# PROJECT_BEL_RUMAH.net
KiCad netlist of a schematic drawn in EAGLE
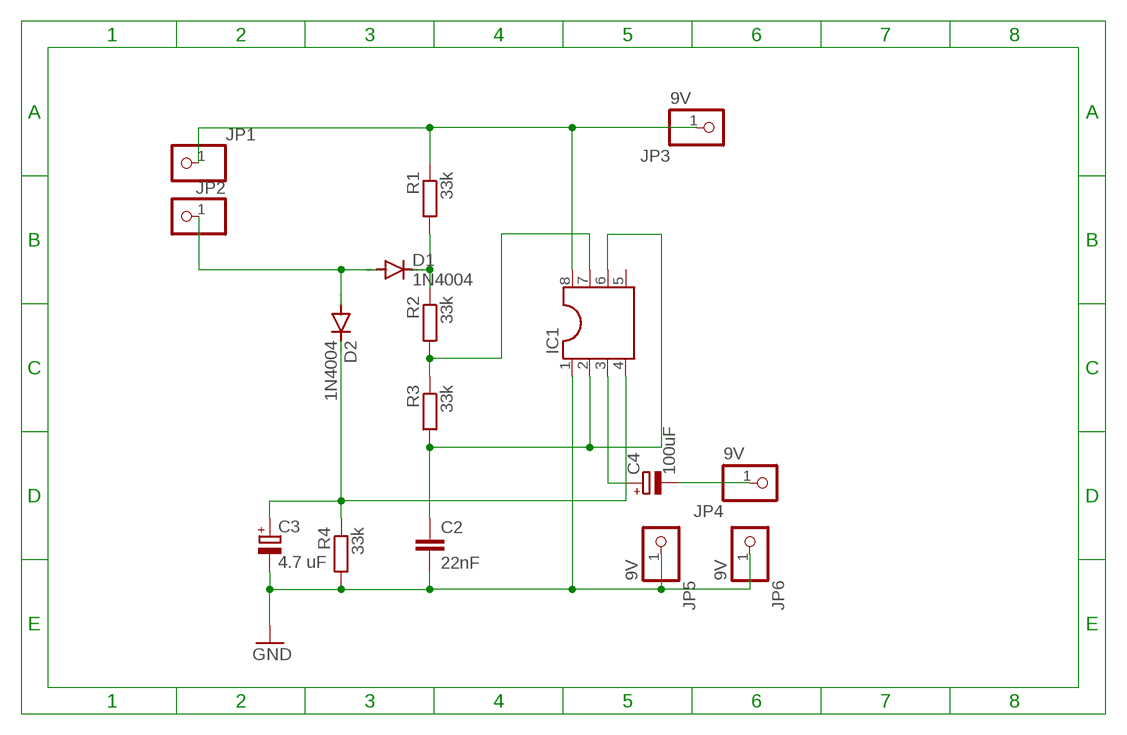
[diagram p0: schematic, sheet 1]

(export (version "E")
  (design (tool "Eeschema 10.0.6"))
  (components
    (comp (ref "C2")
      (value "22nF")
      (footprint "eagle-import:C025-024X044")
      (libsource (lib "eagle-import") (part "C-EU025-024X044"))
    )
    (comp (ref "C3")
      (value "4.7 uF")
      (footprint "eagle-import:E2,5-6E")
      (libsource (lib "eagle-import") (part "CPOL-EUE2,5-6E"))
    )
    (comp (ref "C4")
      (value "100uF")
      (footprint "eagle-import:E2,5-6E")
      (libsource (lib "eagle-import") (part "CPOL-EUE2,5-6E"))
    )
    (comp (ref "D1")
      (value "1N4004")
      (footprint "eagle-import:DO41-10")
      (libsource (lib "eagle-import") (part "1N4004"))
    )
    (comp (ref "D2")
      (value "1N4004")
      (footprint "eagle-import:DO41-10")
      (libsource (lib "eagle-import") (part "1N4004"))
    )
    (comp (ref "IC1")
      (value "DIL8")
      (footprint "eagle-import:DIL08")
      (libsource (lib "eagle-import") (part "DIL8"))
    )
    (comp (ref "JP1")
      (value "PINHD-1X1")
      (footprint "eagle-import:1X01")
      (libsource (lib "eagle-import") (part "PINHD-1X1"))
    )
    (comp (ref "JP2")
      (value "PINHD-1X1")
      (footprint "eagle-import:1X01")
      (libsource (lib "eagle-import") (part "PINHD-1X1"))
    )
    (comp (ref "JP3")
      (value "9V")
      (footprint "eagle-import:1X01")
      (libsource (lib "eagle-import") (part "PINHD-1X1"))
    )
    (comp (ref "JP4")
      (value "9V")
      (footprint "eagle-import:1X01")
      (libsource (lib "eagle-import") (part "PINHD-1X1"))
    )
    (comp (ref "JP5")
      (value "9V")
      (footprint "eagle-import:1X01")
      (libsource (lib "eagle-import") (part "PINHD-1X1"))
    )
    (comp (ref "JP6")
      (value "9V")
      (footprint "eagle-import:1X01")
      (libsource (lib "eagle-import") (part "PINHD-1X1"))
    )
    (comp (ref "R1")
      (value "33k")
      (footprint "eagle-import:0204_5")
      (libsource (lib "eagle-import") (part "R-EU_0204/5"))
    )
    (comp (ref "R2")
      (value "33k")
      (footprint "eagle-import:0204_5")
      (libsource (lib "eagle-import") (part "R-EU_0204/5"))
    )
    (comp (ref "R3")
      (value "33k")
      (footprint "eagle-import:0204_5")
      (libsource (lib "eagle-import") (part "R-EU_0204/5"))
    )
    (comp (ref "R4")
      (value "33k")
      (footprint "eagle-import:0204_5")
      (libsource (lib "eagle-import") (part "R-EU_0204/5"))
    )
  )
  (nets
    (net (code "1") (name "GND") (class "Default")
      (node (ref "C2") (pin "2") (pinfunction "2_2") (pintype "passive"))
      (node (ref "C3") (pin "-") (pinfunction "-_-") (pintype "passive"))
      (node (ref "IC1") (pin "1") (pinfunction "1_1") (pintype "passive"))
      (node (ref "JP5") (pin "1") (pinfunction "1_1") (pintype "passive"))
      (node (ref "JP6") (pin "1") (pinfunction "1_1") (pintype "passive"))
      (node (ref "R4") (pin "2") (pinfunction "2_2") (pintype "passive"))
    )
    (net (code "2") (name "Net-(C2-Pad1)") (class "Default")
      (node (ref "C2") (pin "1") (pinfunction "1_1") (pintype "passive"))
      (node (ref "IC1") (pin "2") (pinfunction "2_2") (pintype "passive"))
      (node (ref "IC1") (pin "6") (pinfunction "6_6") (pintype "passive"))
      (node (ref "R3") (pin "2") (pinfunction "2_2") (pintype "passive"))
    )
    (net (code "3") (name "Net-(C3-Pad+)") (class "Default")
      (node (ref "C3") (pin "+") (pinfunction "+_+") (pintype "passive"))
      (node (ref "D2") (pin "C") (pinfunction "C_C") (pintype "passive"))
      (node (ref "IC1") (pin "4") (pinfunction "4_4") (pintype "passive"))
      (node (ref "R4") (pin "1") (pinfunction "1_1") (pintype "passive"))
    )
    (net (code "4") (name "Net-(C4-Pad+)") (class "Default")
      (node (ref "C4") (pin "+") (pinfunction "+_+") (pintype "passive"))
      (node (ref "IC1") (pin "3") (pinfunction "3_3") (pintype "passive"))
    )
    (net (code "5") (name "Net-(C4-Pad-)") (class "Default")
      (node (ref "C4") (pin "-") (pinfunction "-_-") (pintype "passive"))
      (node (ref "JP4") (pin "1") (pinfunction "1_1") (pintype "passive"))
    )
    (net (code "6") (name "Net-(D1-PadA)") (class "Default")
      (node (ref "D1") (pin "A") (pinfunction "A_A") (pintype "passive"))
      (node (ref "D2") (pin "A") (pinfunction "A_A") (pintype "passive"))
      (node (ref "JP2") (pin "1") (pinfunction "1_1") (pintype "passive"))
    )
    (net (code "7") (name "Net-(D1-PadC)") (class "Default")
      (node (ref "D1") (pin "C") (pinfunction "C_C") (pintype "passive"))
      (node (ref "R1") (pin "2") (pinfunction "2_2") (pintype "passive"))
      (node (ref "R2") (pin "1") (pinfunction "1_1") (pintype "passive"))
    )
    (net (code "8") (name "Net-(IC1-Pad7)") (class "Default")
      (node (ref "IC1") (pin "7") (pinfunction "7_7") (pintype "passive"))
      (node (ref "R2") (pin "2") (pinfunction "2_2") (pintype "passive"))
      (node (ref "R3") (pin "1") (pinfunction "1_1") (pintype "passive"))
    )
    (net (code "9") (name "Net-(IC1-Pad8)") (class "Default")
      (node (ref "IC1") (pin "8") (pinfunction "8_8") (pintype "passive"))
      (node (ref "JP1") (pin "1") (pinfunction "1_1") (pintype "passive"))
      (node (ref "JP3") (pin "1") (pinfunction "1_1") (pintype "passive"))
      (node (ref "R1") (pin "1") (pinfunction "1_1") (pintype "passive"))
    )
    (net (code "10") (name "unconnected-(IC1-Pad5)") (class "Default")
      (node (ref "IC1") (pin "5") (pinfunction "5_5") (pintype "passive"))
    )
  )
)
